# LNA_V3.net
KiCad netlist of a schematic drawn in EAGLE
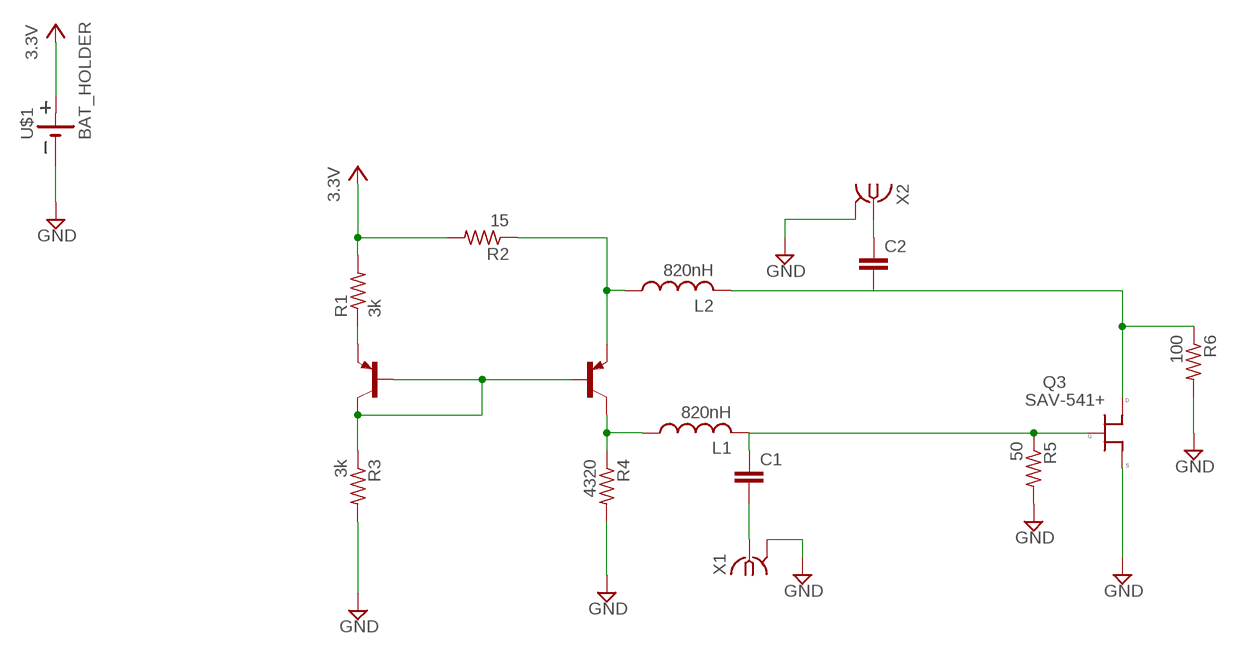
[diagram p0: schematic, sheet 1]

(export (version "E")
  (design (tool "Eeschema 10.0.6"))
  (components
    (comp (ref "C1")
      (value "C-EUC0603")
      (footprint "eagle-import:C0603")
      (libsource (lib "eagle-import") (part "C-EUC0603"))
    )
    (comp (ref "C2")
      (value "C-EUC0603")
      (footprint "eagle-import:C0603")
      (libsource (lib "eagle-import") (part "C-EUC0603"))
    )
    (comp (ref "L1")
      (value "820nH")
      (footprint "eagle-import:L3225M")
      (libsource (lib "eagle-import") (part "L-USL3225M"))
    )
    (comp (ref "L2")
      (value "820nH")
      (footprint "eagle-import:L3225M")
      (libsource (lib "eagle-import") (part "L-USL3225M"))
    )
    (comp (ref "Q1")
      (value "MMBT3906LT1SMD")
      (footprint "eagle-import:SOT23-BEC")
      (libsource (lib "eagle-import") (part "MMBT3906SMDLT1"))
    )
    (comp (ref "Q2")
      (value "MMBT3906LT1SMD")
      (footprint "eagle-import:SOT23-BEC")
      (libsource (lib "eagle-import") (part "MMBT3906SMDLT1"))
    )
    (comp (ref "Q3")
      (value "SAV-541+")
      (footprint "eagle-import:SOT-343")
      (libsource (lib "eagle-import") (part "SAV-541+"))
    )
    (comp (ref "R1")
      (value "3k")
      (footprint "eagle-import:M0805")
      (libsource (lib "eagle-import") (part "R-US_M0805"))
    )
    (comp (ref "R2")
      (value "15")
      (footprint "eagle-import:M0805")
      (libsource (lib "eagle-import") (part "R-US_M0805"))
    )
    (comp (ref "R3")
      (value "3k")
      (footprint "eagle-import:M0805")
      (libsource (lib "eagle-import") (part "R-US_M0805"))
    )
    (comp (ref "R4")
      (value "4320")
      (footprint "eagle-import:M0805")
      (libsource (lib "eagle-import") (part "R-US_M0805"))
    )
    (comp (ref "R5")
      (value "50")
      (footprint "eagle-import:M0805")
      (libsource (lib "eagle-import") (part "R-US_M0805"))
    )
    (comp (ref "R6")
      (value "100")
      (footprint "eagle-import:M0805")
      (libsource (lib "eagle-import") (part "R-US_M0805"))
    )
    (comp (ref "U$1")
      (value "BAT_HOLDER")
      (footprint "eagle-import:BAT_HOLDER")
      (libsource (lib "eagle-import") (part "BAT_HOLDER"))
    )
    (comp (ref "X1")
      (value "SMA-142-0711-821/826")
      (footprint "eagle-import:J502-ND-142-0711-821_826")
      (fields (field (name "MF") "JOHNSON COMPONENTS") (field (name "MPN") "142-0711-821"))
      (libsource (lib "eagle-import") (part "SMA-142-0711-821/826"))
    )
    (comp (ref "X2")
      (value "SMA-142-0711-821/826")
      (footprint "eagle-import:J502-ND-142-0711-821_826")
      (fields (field (name "MF") "JOHNSON COMPONENTS") (field (name "MPN") "142-0711-821"))
      (libsource (lib "eagle-import") (part "SMA-142-0711-821/826"))
    )
  )
  (nets
    (net (code "1") (name "3.3V") (class "Default")
      (node (ref "R1") (pin "2") (pinfunction "2_2") (pintype "passive"))
      (node (ref "R2") (pin "2") (pinfunction "2_2") (pintype "passive"))
      (node (ref "U$1") (pin "P_+") (pinfunction "+_P_+") (pintype "passive"))
    )
    (net (code "2") (name "GND") (class "Default")
      (node (ref "Q3") (pin "2") (pinfunction "S_2") (pintype "passive"))
      (node (ref "Q3") (pin "4") (pinfunction "S_4") (pintype "passive"))
      (node (ref "R3") (pin "2") (pinfunction "2_2") (pintype "passive"))
      (node (ref "R4") (pin "2") (pinfunction "2_2") (pintype "passive"))
      (node (ref "R5") (pin "2") (pinfunction "2_2") (pintype "passive"))
      (node (ref "R6") (pin "2") (pinfunction "2_2") (pintype "passive"))
      (node (ref "U$1") (pin "P_G2") (pinfunction "-_P_G2") (pintype "passive"))
      (node (ref "U$1") (pin "P_G3") (pinfunction "-_P_G3") (pintype "passive"))
      (node (ref "U$1") (pin "P_GND") (pinfunction "-_P_GND") (pintype "passive"))
      (node (ref "X1") (pin "G@1") (pinfunction "2_G@1") (pintype "passive"))
      (node (ref "X1") (pin "G@2") (pinfunction "2_G@2") (pintype "passive"))
      (node (ref "X1") (pin "G@3") (pinfunction "2_G@3") (pintype "passive"))
      (node (ref "X1") (pin "G@4") (pinfunction "2_G@4") (pintype "passive"))
      (node (ref "X2") (pin "G@1") (pinfunction "2_G@1") (pintype "passive"))
      (node (ref "X2") (pin "G@2") (pinfunction "2_G@2") (pintype "passive"))
      (node (ref "X2") (pin "G@3") (pinfunction "2_G@3") (pintype "passive"))
      (node (ref "X2") (pin "G@4") (pinfunction "2_G@4") (pintype "passive"))
    )
    (net (code "3") (name "Net-(C1-Pad2)") (class "Default")
      (node (ref "C1") (pin "2") (pinfunction "2_2") (pintype "passive"))
      (node (ref "X1") (pin "1") (pinfunction "1_1") (pintype "passive"))
    )
    (net (code "4") (name "Net-(C2-Pad1)") (class "Default")
      (node (ref "C2") (pin "1") (pinfunction "1_1") (pintype "passive"))
      (node (ref "X2") (pin "1") (pinfunction "1_1") (pintype "passive"))
    )
    (net (code "5") (name "Net-(L1-Pad1)") (class "Default")
      (node (ref "L1") (pin "1") (pinfunction "1_1") (pintype "passive"))
      (node (ref "Q2") (pin "C") (pinfunction "C_C") (pintype "passive"))
      (node (ref "R4") (pin "1") (pinfunction "1_1") (pintype "passive"))
    )
    (net (code "6") (name "Net-(L2-Pad1)") (class "Default")
      (node (ref "L2") (pin "1") (pinfunction "1_1") (pintype "passive"))
      (node (ref "Q2") (pin "E") (pinfunction "E_E") (pintype "passive"))
      (node (ref "R2") (pin "1") (pinfunction "1_1") (pintype "passive"))
    )
    (net (code "7") (name "Net-(Q1-PadB)") (class "Default")
      (node (ref "Q1") (pin "B") (pinfunction "B_B") (pintype "passive"))
      (node (ref "Q1") (pin "C") (pinfunction "C_C") (pintype "passive"))
      (node (ref "Q2") (pin "B") (pinfunction "B_B") (pintype "passive"))
      (node (ref "R3") (pin "1") (pinfunction "1_1") (pintype "passive"))
    )
    (net (code "8") (name "Net-(Q1-PadE)") (class "Default")
      (node (ref "Q1") (pin "E") (pinfunction "E_E") (pintype "passive"))
      (node (ref "R1") (pin "1") (pinfunction "1_1") (pintype "passive"))
    )
    (net (code "9") (name "Net-(Q3-D)") (class "Default")
      (node (ref "C2") (pin "2") (pinfunction "2_2") (pintype "passive"))
      (node (ref "L2") (pin "2") (pinfunction "2_2") (pintype "passive"))
      (node (ref "Q3") (pin "1") (pinfunction "D_1") (pintype "passive"))
      (node (ref "R6") (pin "1") (pinfunction "1_1") (pintype "passive"))
    )
    (net (code "10") (name "Net-(Q3-G)") (class "Default")
      (node (ref "C1") (pin "1") (pinfunction "1_1") (pintype "passive"))
      (node (ref "L1") (pin "2") (pinfunction "2_2") (pintype "passive"))
      (node (ref "Q3") (pin "3") (pinfunction "G_3") (pintype "passive"))
      (node (ref "R5") (pin "1") (pinfunction "1_1") (pintype "passive"))
    )
    (net (code "11") (name "unconnected-(U$1-PadNC)") (class "Default")
      (node (ref "U$1") (pin "NC") (pinfunction "NC_NC") (pintype "no_connect"))
    )
  )
)
